# 16_seg_display_board.net
KiCad netlist of a schematic drawn in EAGLE
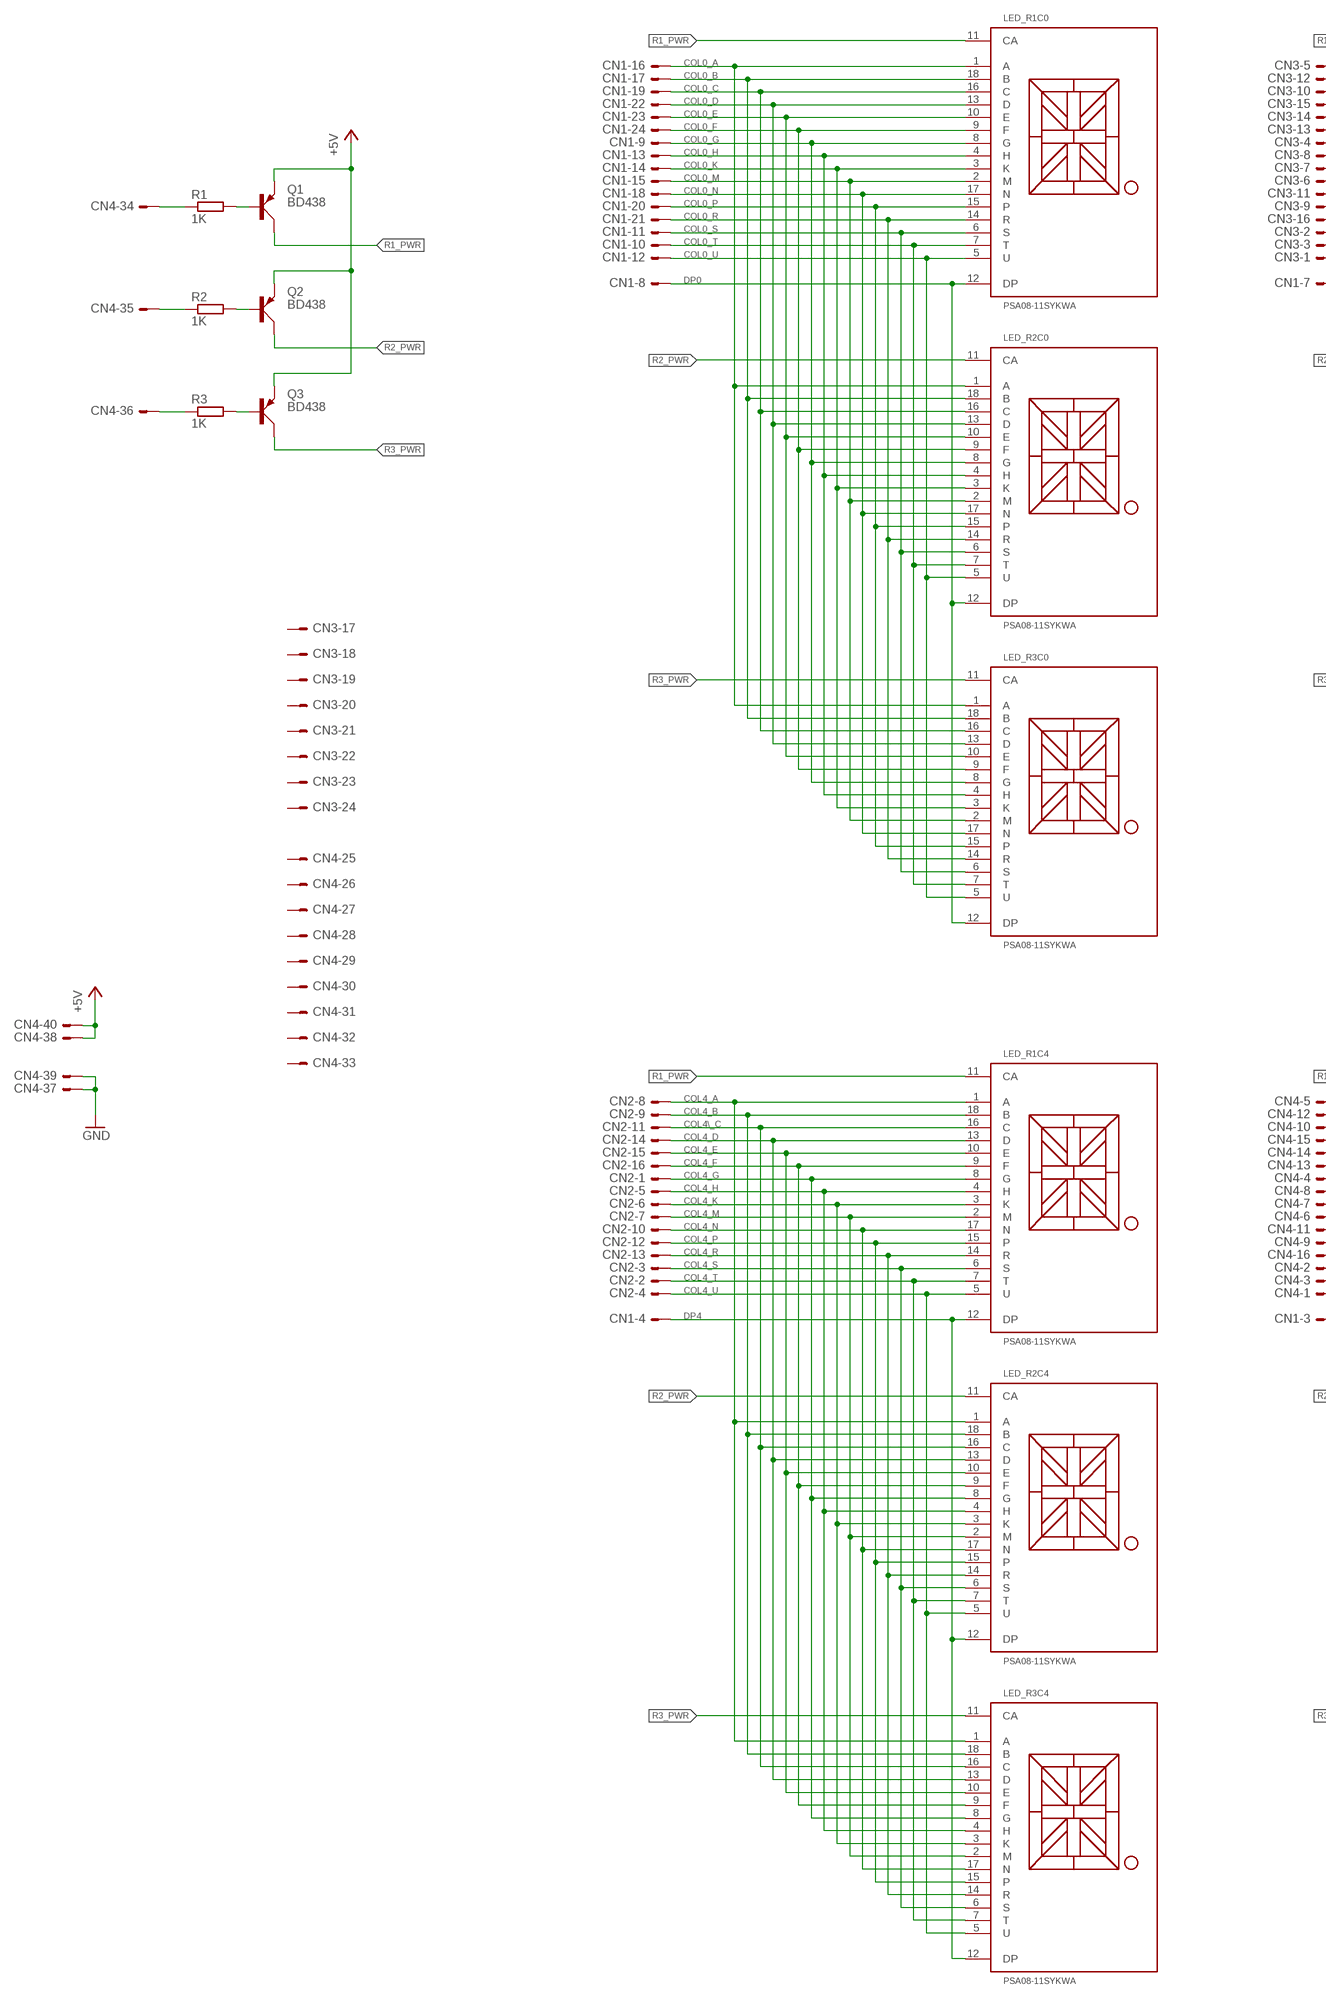
[diagram p0: schematic, sheet 1, part 1 of 2]
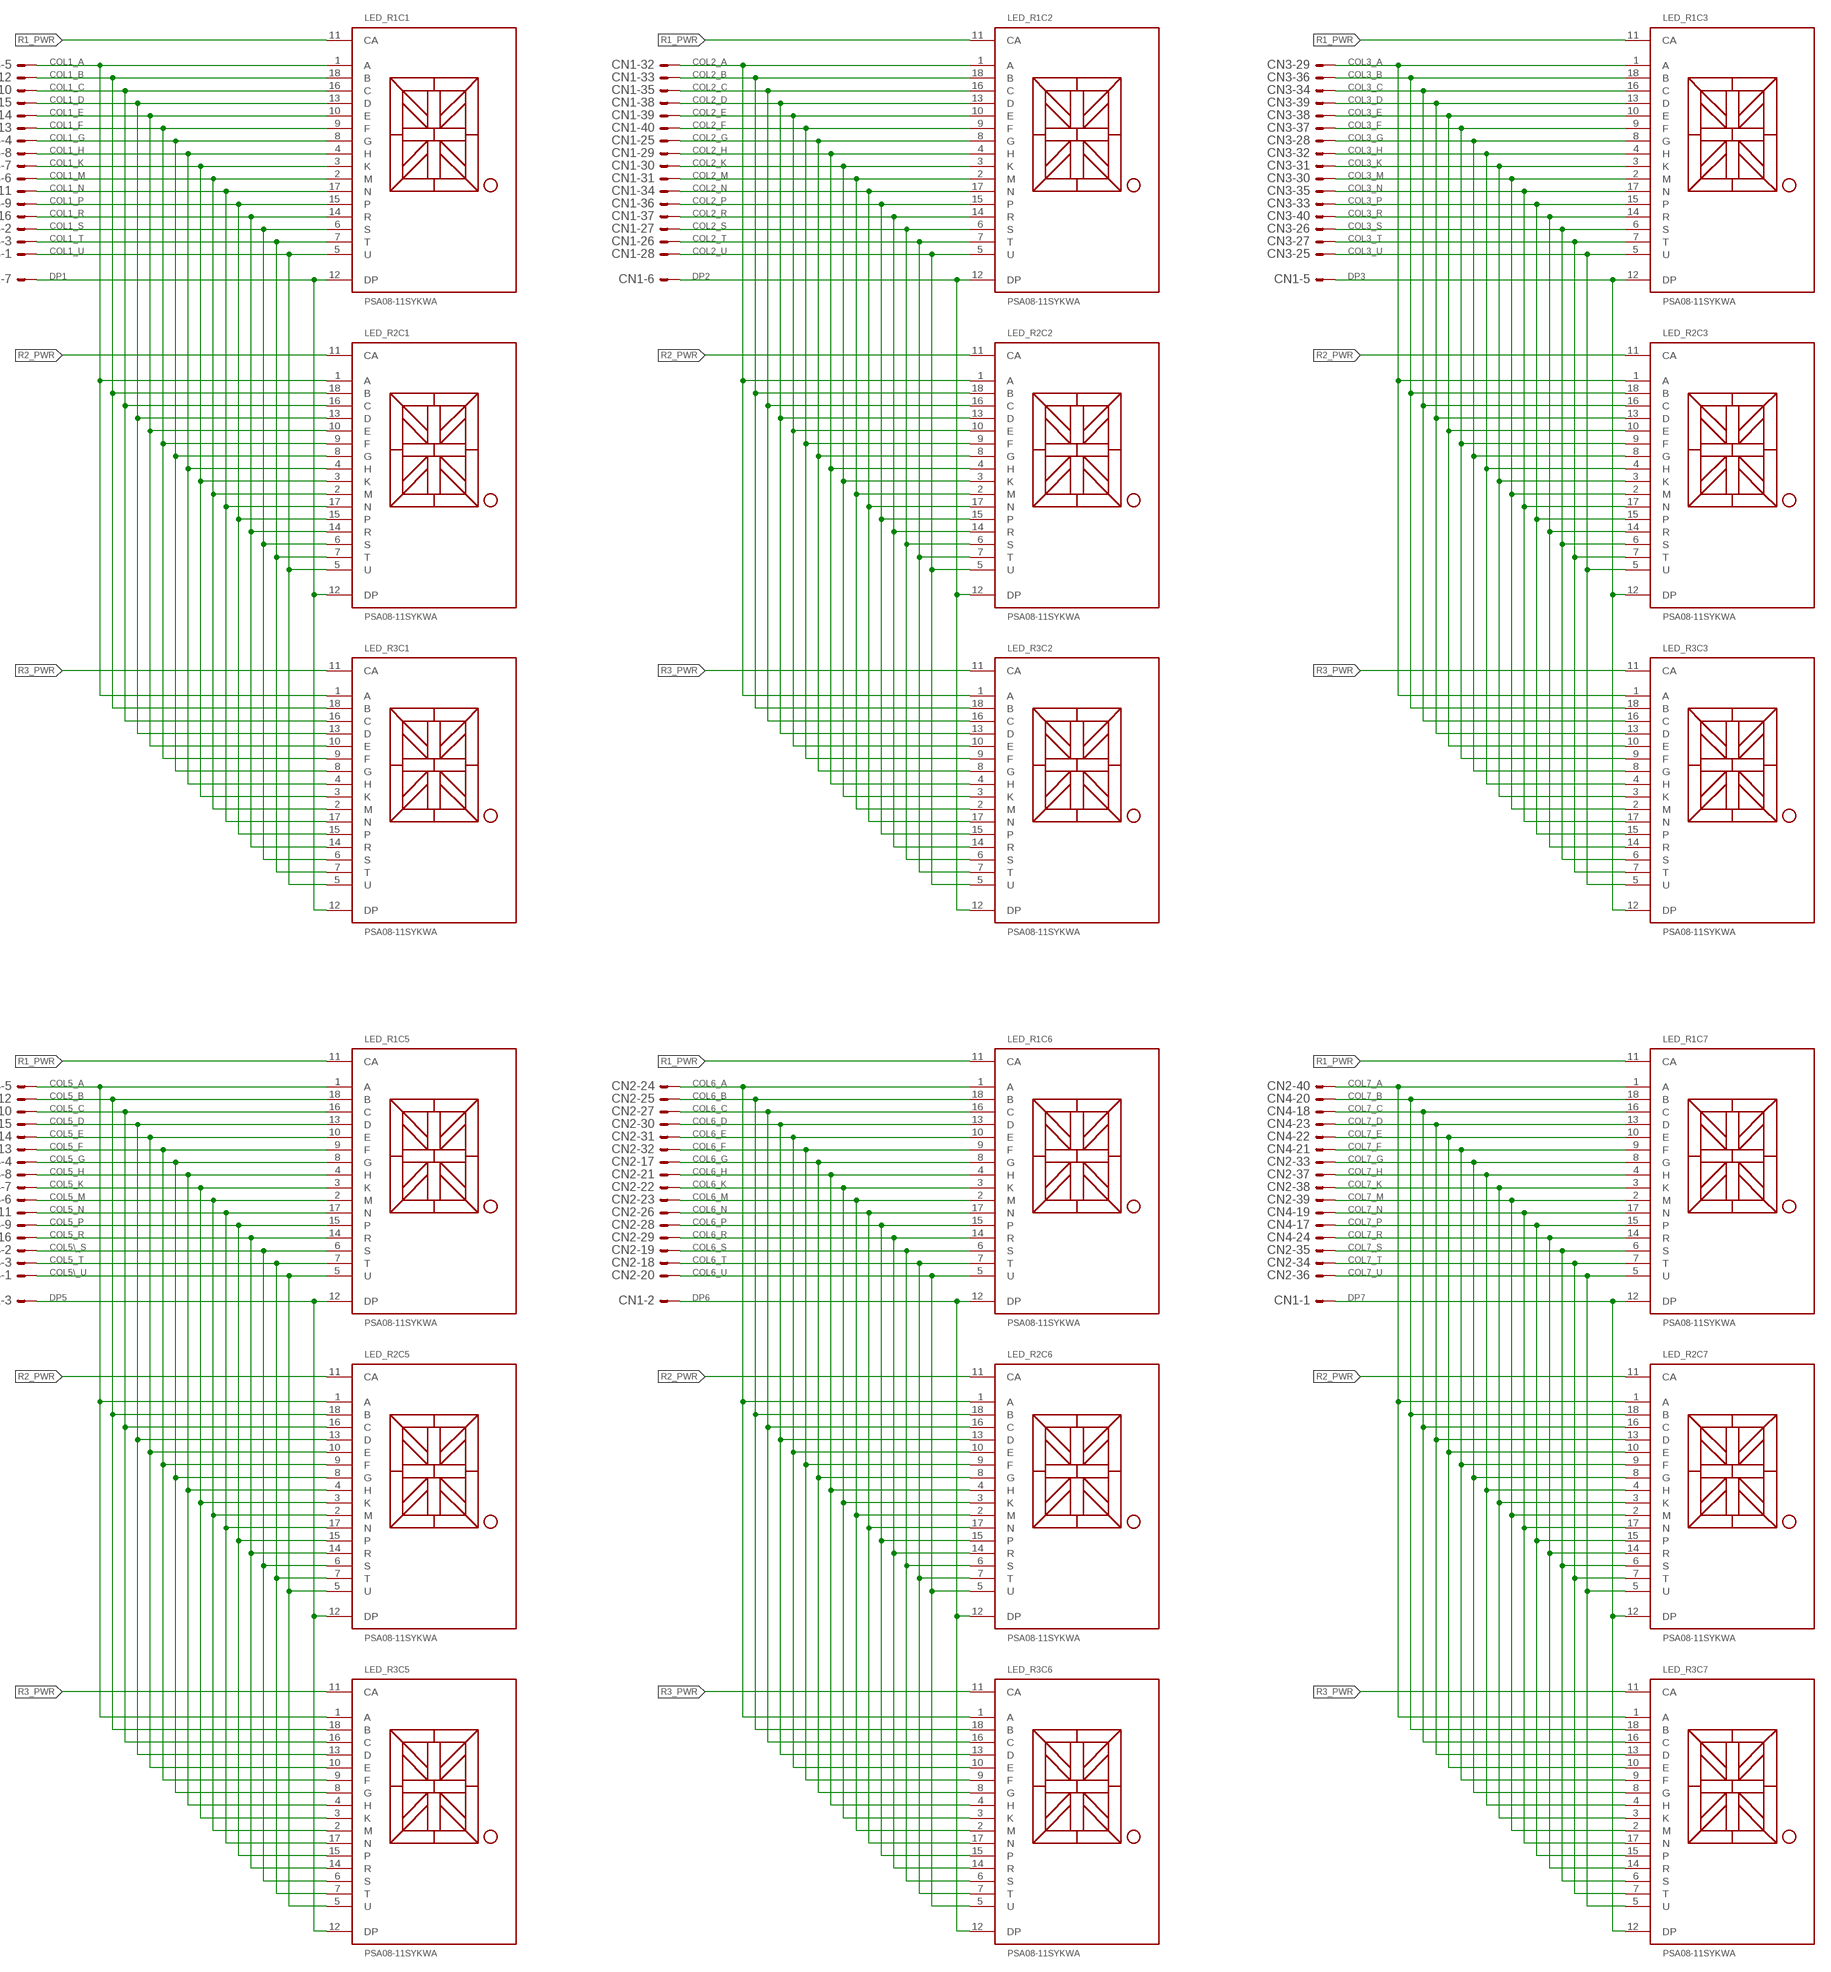
[diagram p1: schematic, sheet 1, part 2 of 2]

(export (version "E")
  (design (tool "Eeschema 10.0.6"))
  (components
    (comp (ref "CN1")
      (value "HDR40")
      (footprint "eagle-import:HDR40")
      (libsource (lib "eagle-import") (part "HDR40"))
    )
    (comp (ref "CN2")
      (value "HDR40")
      (footprint "eagle-import:HDR40")
      (libsource (lib "eagle-import") (part "HDR40"))
    )
    (comp (ref "CN3")
      (value "HDR40")
      (footprint "eagle-import:HDR40")
      (libsource (lib "eagle-import") (part "HDR40"))
    )
    (comp (ref "CN4")
      (value "HDR40")
      (footprint "eagle-import:HDR40")
      (libsource (lib "eagle-import") (part "HDR40"))
    )
    (comp (ref "LED_R1C0")
      (value "PSA08-11SYKWA")
      (footprint "eagle-import:PSA08-11SYKWA")
      (libsource (lib "eagle-import") (part "PSA08-11SYKWA"))
    )
    (comp (ref "LED_R1C1")
      (value "PSA08-11SYKWA")
      (footprint "eagle-import:PSA08-11SYKWA")
      (libsource (lib "eagle-import") (part "PSA08-11SYKWA"))
    )
    (comp (ref "LED_R1C2")
      (value "PSA08-11SYKWA")
      (footprint "eagle-import:PSA08-11SYKWA")
      (libsource (lib "eagle-import") (part "PSA08-11SYKWA"))
    )
    (comp (ref "LED_R1C3")
      (value "PSA08-11SYKWA")
      (footprint "eagle-import:PSA08-11SYKWA")
      (libsource (lib "eagle-import") (part "PSA08-11SYKWA"))
    )
    (comp (ref "LED_R1C4")
      (value "PSA08-11SYKWA")
      (footprint "eagle-import:PSA08-11SYKWA")
      (libsource (lib "eagle-import") (part "PSA08-11SYKWA"))
    )
    (comp (ref "LED_R1C5")
      (value "PSA08-11SYKWA")
      (footprint "eagle-import:PSA08-11SYKWA")
      (libsource (lib "eagle-import") (part "PSA08-11SYKWA"))
    )
    (comp (ref "LED_R1C6")
      (value "PSA08-11SYKWA")
      (footprint "eagle-import:PSA08-11SYKWA")
      (libsource (lib "eagle-import") (part "PSA08-11SYKWA"))
    )
    (comp (ref "LED_R1C7")
      (value "PSA08-11SYKWA")
      (footprint "eagle-import:PSA08-11SYKWA")
      (libsource (lib "eagle-import") (part "PSA08-11SYKWA"))
    )
    (comp (ref "LED_R2C0")
      (value "PSA08-11SYKWA")
      (footprint "eagle-import:PSA08-11SYKWA")
      (libsource (lib "eagle-import") (part "PSA08-11SYKWA"))
    )
    (comp (ref "LED_R2C1")
      (value "PSA08-11SYKWA")
      (footprint "eagle-import:PSA08-11SYKWA")
      (libsource (lib "eagle-import") (part "PSA08-11SYKWA"))
    )
    (comp (ref "LED_R2C2")
      (value "PSA08-11SYKWA")
      (footprint "eagle-import:PSA08-11SYKWA")
      (libsource (lib "eagle-import") (part "PSA08-11SYKWA"))
    )
    (comp (ref "LED_R2C3")
      (value "PSA08-11SYKWA")
      (footprint "eagle-import:PSA08-11SYKWA")
      (libsource (lib "eagle-import") (part "PSA08-11SYKWA"))
    )
    (comp (ref "LED_R2C4")
      (value "PSA08-11SYKWA")
      (footprint "eagle-import:PSA08-11SYKWA")
      (libsource (lib "eagle-import") (part "PSA08-11SYKWA"))
    )
    (comp (ref "LED_R2C5")
      (value "PSA08-11SYKWA")
      (footprint "eagle-import:PSA08-11SYKWA")
      (libsource (lib "eagle-import") (part "PSA08-11SYKWA"))
    )
    (comp (ref "LED_R2C6")
      (value "PSA08-11SYKWA")
      (footprint "eagle-import:PSA08-11SYKWA")
      (libsource (lib "eagle-import") (part "PSA08-11SYKWA"))
    )
    (comp (ref "LED_R2C7")
      (value "PSA08-11SYKWA")
      (footprint "eagle-import:PSA08-11SYKWA")
      (libsource (lib "eagle-import") (part "PSA08-11SYKWA"))
    )
    (comp (ref "LED_R3C0")
      (value "PSA08-11SYKWA")
      (footprint "eagle-import:PSA08-11SYKWA")
      (libsource (lib "eagle-import") (part "PSA08-11SYKWA"))
    )
    (comp (ref "LED_R3C1")
      (value "PSA08-11SYKWA")
      (footprint "eagle-import:PSA08-11SYKWA")
      (libsource (lib "eagle-import") (part "PSA08-11SYKWA"))
    )
    (comp (ref "LED_R3C2")
      (value "PSA08-11SYKWA")
      (footprint "eagle-import:PSA08-11SYKWA")
      (libsource (lib "eagle-import") (part "PSA08-11SYKWA"))
    )
    (comp (ref "LED_R3C3")
      (value "PSA08-11SYKWA")
      (footprint "eagle-import:PSA08-11SYKWA")
      (libsource (lib "eagle-import") (part "PSA08-11SYKWA"))
    )
    (comp (ref "LED_R3C4")
      (value "PSA08-11SYKWA")
      (footprint "eagle-import:PSA08-11SYKWA")
      (libsource (lib "eagle-import") (part "PSA08-11SYKWA"))
    )
    (comp (ref "LED_R3C5")
      (value "PSA08-11SYKWA")
      (footprint "eagle-import:PSA08-11SYKWA")
      (libsource (lib "eagle-import") (part "PSA08-11SYKWA"))
    )
    (comp (ref "LED_R3C6")
      (value "PSA08-11SYKWA")
      (footprint "eagle-import:PSA08-11SYKWA")
      (libsource (lib "eagle-import") (part "PSA08-11SYKWA"))
    )
    (comp (ref "LED_R3C7")
      (value "PSA08-11SYKWA")
      (footprint "eagle-import:PSA08-11SYKWA")
      (libsource (lib "eagle-import") (part "PSA08-11SYKWA"))
    )
    (comp (ref "Q1")
      (value "BD438")
      (footprint "eagle-import:TO126AV")
      (libsource (lib "eagle-import") (part "BD438"))
    )
    (comp (ref "Q2")
      (value "BD438")
      (footprint "eagle-import:TO126AV")
      (libsource (lib "eagle-import") (part "BD438"))
    )
    (comp (ref "Q3")
      (value "BD438")
      (footprint "eagle-import:TO126AV")
      (libsource (lib "eagle-import") (part "BD438"))
    )
    (comp (ref "R1")
      (value "1K")
      (footprint "eagle-import:0207_10")
      (libsource (lib "eagle-import") (part "R-EU_0207/10"))
    )
    (comp (ref "R2")
      (value "1K")
      (footprint "eagle-import:0207_10")
      (libsource (lib "eagle-import") (part "R-EU_0207/10"))
    )
    (comp (ref "R3")
      (value "1K")
      (footprint "eagle-import:0207_10")
      (libsource (lib "eagle-import") (part "R-EU_0207/10"))
    )
  )
  (nets
    (net (code "1") (name "+5V") (class "Default")
      (node (ref "CN4") (pin "38") (pinfunction "S_38") (pintype "passive"))
      (node (ref "CN4") (pin "40") (pinfunction "S_40") (pintype "passive"))
      (node (ref "Q1") (pin "E") (pinfunction "E_E") (pintype "passive"))
      (node (ref "Q2") (pin "E") (pinfunction "E_E") (pintype "passive"))
      (node (ref "Q3") (pin "E") (pinfunction "E_E") (pintype "passive"))
    )
    (net (code "2") (name "/COL0_A") (class "Default")
      (node (ref "CN1") (pin "16") (pinfunction "S_16") (pintype "passive"))
      (node (ref "LED_R1C0") (pin "1") (pinfunction "A_1") (pintype "input"))
      (node (ref "LED_R2C0") (pin "1") (pinfunction "A_1") (pintype "input"))
      (node (ref "LED_R3C0") (pin "1") (pinfunction "A_1") (pintype "input"))
    )
    (net (code "3") (name "/COL0_B") (class "Default")
      (node (ref "CN1") (pin "17") (pinfunction "S_17") (pintype "passive"))
      (node (ref "LED_R1C0") (pin "18") (pinfunction "B_18") (pintype "input"))
      (node (ref "LED_R2C0") (pin "18") (pinfunction "B_18") (pintype "input"))
      (node (ref "LED_R3C0") (pin "18") (pinfunction "B_18") (pintype "input"))
    )
    (net (code "4") (name "/COL0_C") (class "Default")
      (node (ref "CN1") (pin "19") (pinfunction "S_19") (pintype "passive"))
      (node (ref "LED_R1C0") (pin "16") (pinfunction "C_16") (pintype "input"))
      (node (ref "LED_R2C0") (pin "16") (pinfunction "C_16") (pintype "input"))
      (node (ref "LED_R3C0") (pin "16") (pinfunction "C_16") (pintype "input"))
    )
    (net (code "5") (name "/COL0_D") (class "Default")
      (node (ref "CN1") (pin "22") (pinfunction "S_22") (pintype "passive"))
      (node (ref "LED_R1C0") (pin "13") (pinfunction "D_13") (pintype "input"))
      (node (ref "LED_R2C0") (pin "13") (pinfunction "D_13") (pintype "input"))
      (node (ref "LED_R3C0") (pin "13") (pinfunction "D_13") (pintype "input"))
    )
    (net (code "6") (name "/COL0_E") (class "Default")
      (node (ref "CN1") (pin "23") (pinfunction "S_23") (pintype "passive"))
      (node (ref "LED_R1C0") (pin "10") (pinfunction "E_10") (pintype "input"))
      (node (ref "LED_R2C0") (pin "10") (pinfunction "E_10") (pintype "input"))
      (node (ref "LED_R3C0") (pin "10") (pinfunction "E_10") (pintype "input"))
    )
    (net (code "7") (name "/COL0_F") (class "Default")
      (node (ref "CN1") (pin "24") (pinfunction "S_24") (pintype "passive"))
      (node (ref "LED_R1C0") (pin "9") (pinfunction "F_9") (pintype "input"))
      (node (ref "LED_R2C0") (pin "9") (pinfunction "F_9") (pintype "input"))
      (node (ref "LED_R3C0") (pin "9") (pinfunction "F_9") (pintype "input"))
    )
    (net (code "8") (name "/COL0_G") (class "Default")
      (node (ref "CN1") (pin "9") (pinfunction "S_9") (pintype "passive"))
      (node (ref "LED_R1C0") (pin "8") (pinfunction "G_8") (pintype "input"))
      (node (ref "LED_R2C0") (pin "8") (pinfunction "G_8") (pintype "input"))
      (node (ref "LED_R3C0") (pin "8") (pinfunction "G_8") (pintype "input"))
    )
    (net (code "9") (name "/COL0_H") (class "Default")
      (node (ref "CN1") (pin "13") (pinfunction "S_13") (pintype "passive"))
      (node (ref "LED_R1C0") (pin "4") (pinfunction "H_4") (pintype "input"))
      (node (ref "LED_R2C0") (pin "4") (pinfunction "H_4") (pintype "input"))
      (node (ref "LED_R3C0") (pin "4") (pinfunction "H_4") (pintype "input"))
    )
    (net (code "10") (name "/COL0_K") (class "Default")
      (node (ref "CN1") (pin "14") (pinfunction "S_14") (pintype "passive"))
      (node (ref "LED_R1C0") (pin "3") (pinfunction "K_3") (pintype "input"))
      (node (ref "LED_R2C0") (pin "3") (pinfunction "K_3") (pintype "input"))
      (node (ref "LED_R3C0") (pin "3") (pinfunction "K_3") (pintype "input"))
    )
    (net (code "11") (name "/COL0_M") (class "Default")
      (node (ref "CN1") (pin "15") (pinfunction "S_15") (pintype "passive"))
      (node (ref "LED_R1C0") (pin "2") (pinfunction "M_2") (pintype "input"))
      (node (ref "LED_R2C0") (pin "2") (pinfunction "M_2") (pintype "input"))
      (node (ref "LED_R3C0") (pin "2") (pinfunction "M_2") (pintype "input"))
    )
    (net (code "12") (name "/COL0_N") (class "Default")
      (node (ref "CN1") (pin "18") (pinfunction "S_18") (pintype "passive"))
      (node (ref "LED_R1C0") (pin "17") (pinfunction "N_17") (pintype "input"))
      (node (ref "LED_R2C0") (pin "17") (pinfunction "N_17") (pintype "input"))
      (node (ref "LED_R3C0") (pin "17") (pinfunction "N_17") (pintype "input"))
    )
    (net (code "13") (name "/COL0_P") (class "Default")
      (node (ref "CN1") (pin "20") (pinfunction "S_20") (pintype "passive"))
      (node (ref "LED_R1C0") (pin "15") (pinfunction "P_15") (pintype "input"))
      (node (ref "LED_R2C0") (pin "15") (pinfunction "P_15") (pintype "input"))
      (node (ref "LED_R3C0") (pin "15") (pinfunction "P_15") (pintype "input"))
    )
    (net (code "14") (name "/COL0_R") (class "Default")
      (node (ref "CN1") (pin "21") (pinfunction "S_21") (pintype "passive"))
      (node (ref "LED_R1C0") (pin "14") (pinfunction "R_14") (pintype "input"))
      (node (ref "LED_R2C0") (pin "14") (pinfunction "R_14") (pintype "input"))
      (node (ref "LED_R3C0") (pin "14") (pinfunction "R_14") (pintype "input"))
    )
    (net (code "15") (name "/COL0_S") (class "Default")
      (node (ref "CN1") (pin "11") (pinfunction "S_11") (pintype "passive"))
      (node (ref "LED_R1C0") (pin "6") (pinfunction "S_6") (pintype "input"))
      (node (ref "LED_R2C0") (pin "6") (pinfunction "S_6") (pintype "input"))
      (node (ref "LED_R3C0") (pin "6") (pinfunction "S_6") (pintype "input"))
    )
    (net (code "16") (name "/COL0_T") (class "Default")
      (node (ref "CN1") (pin "10") (pinfunction "S_10") (pintype "passive"))
      (node (ref "LED_R1C0") (pin "7") (pinfunction "T_7") (pintype "input"))
      (node (ref "LED_R2C0") (pin "7") (pinfunction "T_7") (pintype "input"))
      (node (ref "LED_R3C0") (pin "7") (pinfunction "T_7") (pintype "input"))
    )
    (net (code "17") (name "/COL0_U") (class "Default")
      (node (ref "CN1") (pin "12") (pinfunction "S_12") (pintype "passive"))
      (node (ref "LED_R1C0") (pin "5") (pinfunction "U_5") (pintype "input"))
      (node (ref "LED_R2C0") (pin "5") (pinfunction "U_5") (pintype "input"))
      (node (ref "LED_R3C0") (pin "5") (pinfunction "U_5") (pintype "input"))
    )
    (net (code "18") (name "/COL1_A") (class "Default")
      (node (ref "CN3") (pin "5") (pinfunction "S_5") (pintype "passive"))
      (node (ref "LED_R1C1") (pin "1") (pinfunction "A_1") (pintype "input"))
      (node (ref "LED_R2C1") (pin "1") (pinfunction "A_1") (pintype "input"))
      (node (ref "LED_R3C1") (pin "1") (pinfunction "A_1") (pintype "input"))
    )
    (net (code "19") (name "/COL1_B") (class "Default")
      (node (ref "CN3") (pin "12") (pinfunction "S_12") (pintype "passive"))
      (node (ref "LED_R1C1") (pin "18") (pinfunction "B_18") (pintype "input"))
      (node (ref "LED_R2C1") (pin "18") (pinfunction "B_18") (pintype "input"))
      (node (ref "LED_R3C1") (pin "18") (pinfunction "B_18") (pintype "input"))
    )
    (net (code "20") (name "/COL1_C") (class "Default")
      (node (ref "CN3") (pin "10") (pinfunction "S_10") (pintype "passive"))
      (node (ref "LED_R1C1") (pin "16") (pinfunction "C_16") (pintype "input"))
      (node (ref "LED_R2C1") (pin "16") (pinfunction "C_16") (pintype "input"))
      (node (ref "LED_R3C1") (pin "16") (pinfunction "C_16") (pintype "input"))
    )
    (net (code "21") (name "/COL1_D") (class "Default")
      (node (ref "CN3") (pin "15") (pinfunction "S_15") (pintype "passive"))
      (node (ref "LED_R1C1") (pin "13") (pinfunction "D_13") (pintype "input"))
      (node (ref "LED_R2C1") (pin "13") (pinfunction "D_13") (pintype "input"))
      (node (ref "LED_R3C1") (pin "13") (pinfunction "D_13") (pintype "input"))
    )
    (net (code "22") (name "/COL1_E") (class "Default")
      (node (ref "CN3") (pin "14") (pinfunction "S_14") (pintype "passive"))
      (node (ref "LED_R1C1") (pin "10") (pinfunction "E_10") (pintype "input"))
      (node (ref "LED_R2C1") (pin "10") (pinfunction "E_10") (pintype "input"))
      (node (ref "LED_R3C1") (pin "10") (pinfunction "E_10") (pintype "input"))
    )
    (net (code "23") (name "/COL1_F") (class "Default")
      (node (ref "CN3") (pin "13") (pinfunction "S_13") (pintype "passive"))
      (node (ref "LED_R1C1") (pin "9") (pinfunction "F_9") (pintype "input"))
      (node (ref "LED_R2C1") (pin "9") (pinfunction "F_9") (pintype "input"))
      (node (ref "LED_R3C1") (pin "9") (pinfunction "F_9") (pintype "input"))
    )
    (net (code "24") (name "/COL1_G") (class "Default")
      (node (ref "CN3") (pin "4") (pinfunction "S_4") (pintype "passive"))
      (node (ref "LED_R1C1") (pin "8") (pinfunction "G_8") (pintype "input"))
      (node (ref "LED_R2C1") (pin "8") (pinfunction "G_8") (pintype "input"))
      (node (ref "LED_R3C1") (pin "8") (pinfunction "G_8") (pintype "input"))
    )
    (net (code "25") (name "/COL1_H") (class "Default")
      (node (ref "CN3") (pin "8") (pinfunction "S_8") (pintype "passive"))
      (node (ref "LED_R1C1") (pin "4") (pinfunction "H_4") (pintype "input"))
      (node (ref "LED_R2C1") (pin "4") (pinfunction "H_4") (pintype "input"))
      (node (ref "LED_R3C1") (pin "4") (pinfunction "H_4") (pintype "input"))
    )
    (net (code "26") (name "/COL1_K") (class "Default")
      (node (ref "CN3") (pin "7") (pinfunction "S_7") (pintype "passive"))
      (node (ref "LED_R1C1") (pin "3") (pinfunction "K_3") (pintype "input"))
      (node (ref "LED_R2C1") (pin "3") (pinfunction "K_3") (pintype "input"))
      (node (ref "LED_R3C1") (pin "3") (pinfunction "K_3") (pintype "input"))
    )
    (net (code "27") (name "/COL1_M") (class "Default")
      (node (ref "CN3") (pin "6") (pinfunction "S_6") (pintype "passive"))
      (node (ref "LED_R1C1") (pin "2") (pinfunction "M_2") (pintype "input"))
      (node (ref "LED_R2C1") (pin "2") (pinfunction "M_2") (pintype "input"))
      (node (ref "LED_R3C1") (pin "2") (pinfunction "M_2") (pintype "input"))
    )
    (net (code "28") (name "/COL1_N") (class "Default")
      (node (ref "CN3") (pin "11") (pinfunction "S_11") (pintype "passive"))
      (node (ref "LED_R1C1") (pin "17") (pinfunction "N_17") (pintype "input"))
      (node (ref "LED_R2C1") (pin "17") (pinfunction "N_17") (pintype "input"))
      (node (ref "LED_R3C1") (pin "17") (pinfunction "N_17") (pintype "input"))
    )
    (net (code "29") (name "/COL1_P") (class "Default")
      (node (ref "CN3") (pin "9") (pinfunction "S_9") (pintype "passive"))
      (node (ref "LED_R1C1") (pin "15") (pinfunction "P_15") (pintype "input"))
      (node (ref "LED_R2C1") (pin "15") (pinfunction "P_15") (pintype "input"))
      (node (ref "LED_R3C1") (pin "15") (pinfunction "P_15") (pintype "input"))
    )
    (net (code "30") (name "/COL1_R") (class "Default")
      (node (ref "CN3") (pin "16") (pinfunction "S_16") (pintype "passive"))
      (node (ref "LED_R1C1") (pin "14") (pinfunction "R_14") (pintype "input"))
      (node (ref "LED_R2C1") (pin "14") (pinfunction "R_14") (pintype "input"))
      (node (ref "LED_R3C1") (pin "14") (pinfunction "R_14") (pintype "input"))
    )
    (net (code "31") (name "/COL1_S") (class "Default")
      (node (ref "CN3") (pin "2") (pinfunction "S_2") (pintype "passive"))
      (node (ref "LED_R1C1") (pin "6") (pinfunction "S_6") (pintype "input"))
      (node (ref "LED_R2C1") (pin "6") (pinfunction "S_6") (pintype "input"))
      (node (ref "LED_R3C1") (pin "6") (pinfunction "S_6") (pintype "input"))
    )
    (net (code "32") (name "/COL1_T") (class "Default")
      (node (ref "CN3") (pin "3") (pinfunction "S_3") (pintype "passive"))
      (node (ref "LED_R1C1") (pin "7") (pinfunction "T_7") (pintype "input"))
      (node (ref "LED_R2C1") (pin "7") (pinfunction "T_7") (pintype "input"))
      (node (ref "LED_R3C1") (pin "7") (pinfunction "T_7") (pintype "input"))
    )
    (net (code "33") (name "/COL1_U") (class "Default")
      (node (ref "CN3") (pin "1") (pinfunction "S_1") (pintype "passive"))
      (node (ref "LED_R1C1") (pin "5") (pinfunction "U_5") (pintype "input"))
      (node (ref "LED_R2C1") (pin "5") (pinfunction "U_5") (pintype "input"))
      (node (ref "LED_R3C1") (pin "5") (pinfunction "U_5") (pintype "input"))
    )
    (net (code "34") (name "/COL2_A") (class "Default")
      (node (ref "CN1") (pin "32") (pinfunction "S_32") (pintype "passive"))
      (node (ref "LED_R1C2") (pin "1") (pinfunction "A_1") (pintype "input"))
      (node (ref "LED_R2C2") (pin "1") (pinfunction "A_1") (pintype "input"))
      (node (ref "LED_R3C2") (pin "1") (pinfunction "A_1") (pintype "input"))
    )
    (net (code "35") (name "/COL2_B") (class "Default")
      (node (ref "CN1") (pin "33") (pinfunction "S_33") (pintype "passive"))
      (node (ref "LED_R1C2") (pin "18") (pinfunction "B_18") (pintype "input"))
      (node (ref "LED_R2C2") (pin "18") (pinfunction "B_18") (pintype "input"))
      (node (ref "LED_R3C2") (pin "18") (pinfunction "B_18") (pintype "input"))
    )
    (net (code "36") (name "/COL2_C") (class "Default")
      (node (ref "CN1") (pin "35") (pinfunction "S_35") (pintype "passive"))
      (node (ref "LED_R1C2") (pin "16") (pinfunction "C_16") (pintype "input"))
      (node (ref "LED_R2C2") (pin "16") (pinfunction "C_16") (pintype "input"))
      (node (ref "LED_R3C2") (pin "16") (pinfunction "C_16") (pintype "input"))
    )
    (net (code "37") (name "/COL2_D") (class "Default")
      (node (ref "CN1") (pin "38") (pinfunction "S_38") (pintype "passive"))
      (node (ref "LED_R1C2") (pin "13") (pinfunction "D_13") (pintype "input"))
      (node (ref "LED_R2C2") (pin "13") (pinfunction "D_13") (pintype "input"))
      (node (ref "LED_R3C2") (pin "13") (pinfunction "D_13") (pintype "input"))
    )
    (net (code "38") (name "/COL2_E") (class "Default")
      (node (ref "CN1") (pin "39") (pinfunction "S_39") (pintype "passive"))
      (node (ref "LED_R1C2") (pin "10") (pinfunction "E_10") (pintype "input"))
      (node (ref "LED_R2C2") (pin "10") (pinfunction "E_10") (pintype "input"))
      (node (ref "LED_R3C2") (pin "10") (pinfunction "E_10") (pintype "input"))
    )
    (net (code "39") (name "/COL2_F") (class "Default")
      (node (ref "CN1") (pin "40") (pinfunction "S_40") (pintype "passive"))
      (node (ref "LED_R1C2") (pin "9") (pinfunction "F_9") (pintype "input"))
      (node (ref "LED_R2C2") (pin "9") (pinfunction "F_9") (pintype "input"))
      (node (ref "LED_R3C2") (pin "9") (pinfunction "F_9") (pintype "input"))
    )
    (net (code "40") (name "/COL2_G") (class "Default")
      (node (ref "CN1") (pin "25") (pinfunction "S_25") (pintype "passive"))
      (node (ref "LED_R1C2") (pin "8") (pinfunction "G_8") (pintype "input"))
      (node (ref "LED_R2C2") (pin "8") (pinfunction "G_8") (pintype "input"))
      (node (ref "LED_R3C2") (pin "8") (pinfunction "G_8") (pintype "input"))
    )
    (net (code "41") (name "/COL2_H") (class "Default")
      (node (ref "CN1") (pin "29") (pinfunction "S_29") (pintype "passive"))
      (node (ref "LED_R1C2") (pin "4") (pinfunction "H_4") (pintype "input"))
      (node (ref "LED_R2C2") (pin "4") (pinfunction "H_4") (pintype "input"))
      (node (ref "LED_R3C2") (pin "4") (pinfunction "H_4") (pintype "input"))
    )
    (net (code "42") (name "/COL2_K") (class "Default")
      (node (ref "CN1") (pin "30") (pinfunction "S_30") (pintype "passive"))
      (node (ref "LED_R1C2") (pin "3") (pinfunction "K_3") (pintype "input"))
      (node (ref "LED_R2C2") (pin "3") (pinfunction "K_3") (pintype "input"))
      (node (ref "LED_R3C2") (pin "3") (pinfunction "K_3") (pintype "input"))
    )
    (net (code "43") (name "/COL2_M") (class "Default")
      (node (ref "CN1") (pin "31") (pinfunction "S_31") (pintype "passive"))
      (node (ref "LED_R1C2") (pin "2") (pinfunction "M_2") (pintype "input"))
      (node (ref "LED_R2C2") (pin "2") (pinfunction "M_2") (pintype "input"))
      (node (ref "LED_R3C2") (pin "2") (pinfunction "M_2") (pintype "input"))
    )
    (net (code "44") (name "/COL2_N") (class "Default")
      (node (ref "CN1") (pin "34") (pinfunction "S_34") (pintype "passive"))
      (node (ref "LED_R1C2") (pin "17") (pinfunction "N_17") (pintype "input"))
      (node (ref "LED_R2C2") (pin "17") (pinfunction "N_17") (pintype "input"))
      (node (ref "LED_R3C2") (pin "17") (pinfunction "N_17") (pintype "input"))
    )
    (net (code "45") (name "/COL2_P") (class "Default")
      (node (ref "CN1") (pin "36") (pinfunction "S_36") (pintype "passive"))
      (node (ref "LED_R1C2") (pin "15") (pinfunction "P_15") (pintype "input"))
      (node (ref "LED_R2C2") (pin "15") (pinfunction "P_15") (pintype "input"))
      (node (ref "LED_R3C2") (pin "15") (pinfunction "P_15") (pintype "input"))
    )
    (net (code "46") (name "/COL2_R") (class "Default")
      (node (ref "CN1") (pin "37") (pinfunction "S_37") (pintype "passive"))
      (node (ref "LED_R1C2") (pin "14") (pinfunction "R_14") (pintype "input"))
      (node (ref "LED_R2C2") (pin "14") (pinfunction "R_14") (pintype "input"))
      (node (ref "LED_R3C2") (pin "14") (pinfunction "R_14") (pintype "input"))
    )
    (net (code "47") (name "/COL2_S") (class "Default")
      (node (ref "CN1") (pin "27") (pinfunction "S_27") (pintype "passive"))
      (node (ref "LED_R1C2") (pin "6") (pinfunction "S_6") (pintype "input"))
      (node (ref "LED_R2C2") (pin "6") (pinfunction "S_6") (pintype "input"))
      (node (ref "LED_R3C2") (pin "6") (pinfunction "S_6") (pintype "input"))
    )
    (net (code "48") (name "/COL2_T") (class "Default")
      (node (ref "CN1") (pin "26") (pinfunction "S_26") (pintype "passive"))
      (node (ref "LED_R1C2") (pin "7") (pinfunction "T_7") (pintype "input"))
      (node (ref "LED_R2C2") (pin "7") (pinfunction "T_7") (pintype "input"))
      (node (ref "LED_R3C2") (pin "7") (pinfunction "T_7") (pintype "input"))
    )
    (net (code "49") (name "/COL2_U") (class "Default")
      (node (ref "CN1") (pin "28") (pinfunction "S_28") (pintype "passive"))
      (node (ref "LED_R1C2") (pin "5") (pinfunction "U_5") (pintype "input"))
      (node (ref "LED_R2C2") (pin "5") (pinfunction "U_5") (pintype "input"))
      (node (ref "LED_R3C2") (pin "5") (pinfunction "U_5") (pintype "input"))
    )
    (net (code "50") (name "/COL3_A") (class "Default")
      (node (ref "CN3") (pin "29") (pinfunction "S_29") (pintype "passive"))
      (node (ref "LED_R1C3") (pin "1") (pinfunction "A_1") (pintype "input"))
      (node (ref "LED_R2C3") (pin "1") (pinfunction "A_1") (pintype "input"))
      (node (ref "LED_R3C3") (pin "1") (pinfunction "A_1") (pintype "input"))
    )
    (net (code "51") (name "/COL3_B") (class "Default")
      (node (ref "CN3") (pin "36") (pinfunction "S_36") (pintype "passive"))
      (node (ref "LED_R1C3") (pin "18") (pinfunction "B_18") (pintype "input"))
      (node (ref "LED_R2C3") (pin "18") (pinfunction "B_18") (pintype "input"))
      (node (ref "LED_R3C3") (pin "18") (pinfunction "B_18") (pintype "input"))
    )
    (net (code "52") (name "/COL3_C") (class "Default")
      (node (ref "CN3") (pin "34") (pinfunction "S_34") (pintype "passive"))
      (node (ref "LED_R1C3") (pin "16") (pinfunction "C_16") (pintype "input"))
      (node (ref "LED_R2C3") (pin "16") (pinfunction "C_16") (pintype "input"))
      (node (ref "LED_R3C3") (pin "16") (pinfunction "C_16") (pintype "input"))
    )
    (net (code "53") (name "/COL3_D") (class "Default")
      (node (ref "CN3") (pin "39") (pinfunction "S_39") (pintype "passive"))
      (node (ref "LED_R1C3") (pin "13") (pinfunction "D_13") (pintype "input"))
      (node (ref "LED_R2C3") (pin "13") (pinfunction "D_13") (pintype "input"))
      (node (ref "LED_R3C3") (pin "13") (pinfunction "D_13") (pintype "input"))
    )
    (net (code "54") (name "/COL3_E") (class "Default")
      (node (ref "CN3") (pin "38") (pinfunction "S_38") (pintype "passive"))
      (node (ref "LED_R1C3") (pin "10") (pinfunction "E_10") (pintype "input"))
      (node (ref "LED_R2C3") (pin "10") (pinfunction "E_10") (pintype "input"))
      (node (ref "LED_R3C3") (pin "10") (pinfunction "E_10") (pintype "input"))
    )
    (net (code "55") (name "/COL3_F") (class "Default")
      (node (ref "CN3") (pin "37") (pinfunction "S_37") (pintype "passive"))
      (node (ref "LED_R1C3") (pin "9") (pinfunction "F_9") (pintype "input"))
      (node (ref "LED_R2C3") (pin "9") (pinfunction "F_9") (pintype "input"))
      (node (ref "LED_R3C3") (pin "9") (pinfunction "F_9") (pintype "input"))
    )
    (net (code "56") (name "/COL3_G") (class "Default")
      (node (ref "CN3") (pin "28") (pinfunction "S_28") (pintype "passive"))
      (node (ref "LED_R1C3") (pin "8") (pinfunction "G_8") (pintype "input"))
      (node (ref "LED_R2C3") (pin "8") (pinfunction "G_8") (pintype "input"))
      (node (ref "LED_R3C3") (pin "8") (pinfunction "G_8") (pintype "input"))
    )
    (net (code "57") (name "/COL3_H") (class "Default")
      (node (ref "CN3") (pin "32") (pinfunction "S_32") (pintype "passive"))
      (node (ref "LED_R1C3") (pin "4") (pinfunction "H_4") (pintype "input"))
      (node (ref "LED_R2C3") (pin "4") (pinfunction "H_4") (pintype "input"))
      (node (ref "LED_R3C3") (pin "4") (pinfunction "H_4") (pintype "input"))
    )
    (net (code "58") (name "/COL3_K") (class "Default")
      (node (ref "CN3") (pin "31") (pinfunction "S_31") (pintype "passive"))
      (node (ref "LED_R1C3") (pin "3") (pinfunction "K_3") (pintype "input"))
      (node (ref "LED_R2C3") (pin "3") (pinfunction "K_3") (pintype "input"))
      (node (ref "LED_R3C3") (pin "3") (pinfunction "K_3") (pintype "input"))
    )
    (net (code "59") (name "/COL3_M") (class "Default")
      (node (ref "CN3") (pin "30") (pinfunction "S_30") (pintype "passive"))
      (node (ref "LED_R1C3") (pin "2") (pinfunction "M_2") (pintype "input"))
      (node (ref "LED_R2C3") (pin "2") (pinfunction "M_2") (pintype "input"))
      (node (ref "LED_R3C3") (pin "2") (pinfunction "M_2") (pintype "input"))
    )
    (net (code "60") (name "/COL3_N") (class "Default")
      (node (ref "CN3") (pin "35") (pinfunction "S_35") (pintype "passive"))
      (node (ref "LED_R1C3") (pin "17") (pinfunction "N_17") (pintype "input"))
      (node (ref "LED_R2C3") (pin "17") (pinfunction "N_17") (pintype "input"))
      (node (ref "LED_R3C3") (pin "17") (pinfunction "N_17") (pintype "input"))
    )
    (net (code "61") (name "/COL3_P") (class "Default")
      (node (ref "CN3") (pin "33") (pinfunction "S_33") (pintype "passive"))
      (node (ref "LED_R1C3") (pin "15") (pinfunction "P_15") (pintype "input"))
      (node (ref "LED_R2C3") (pin "15") (pinfunction "P_15") (pintype "input"))
      (node (ref "LED_R3C3") (pin "15") (pinfunction "P_15") (pintype "input"))
    )
    (net (code "62") (name "/COL3_R") (class "Default")
      (node (ref "CN3") (pin "40") (pinfunction "S_40") (pintype "passive"))
      (node (ref "LED_R1C3") (pin "14") (pinfunction "R_14") (pintype "input"))
      (node (ref "LED_R2C3") (pin "14") (pinfunction "R_14") (pintype "input"))
      (node (ref "LED_R3C3") (pin "14") (pinfunction "R_14") (pintype "input"))
    )
    (net (code "63") (name "/COL3_S") (class "Default")
      (node (ref "CN3") (pin "26") (pinfunction "S_26") (pintype "passive"))
      (node (ref "LED_R1C3") (pin "6") (pinfunction "S_6") (pintype "input"))
      (node (ref "LED_R2C3") (pin "6") (pinfunction "S_6") (pintype "input"))
      (node (ref "LED_R3C3") (pin "6") (pinfunction "S_6") (pintype "input"))
    )
    (net (code "64") (name "/COL3_T") (class "Default")
      (node (ref "CN3") (pin "27") (pinfunction "S_27") (pintype "passive"))
      (node (ref "LED_R1C3") (pin "7") (pinfunction "T_7") (pintype "input"))
      (node (ref "LED_R2C3") (pin "7") (pinfunction "T_7") (pintype "input"))
      (node (ref "LED_R3C3") (pin "7") (pinfunction "T_7") (pintype "input"))
    )
    (net (code "65") (name "/COL3_U") (class "Default")
      (node (ref "CN3") (pin "25") (pinfunction "S_25") (pintype "passive"))
      (node (ref "LED_R1C3") (pin "5") (pinfunction "U_5") (pintype "input"))
      (node (ref "LED_R2C3") (pin "5") (pinfunction "U_5") (pintype "input"))
      (node (ref "LED_R3C3") (pin "5") (pinfunction "U_5") (pintype "input"))
    )
    (net (code "66") (name "/COL4\\_C") (class "Default")
      (node (ref "CN2") (pin "11") (pinfunction "S_11") (pintype "passive"))
      (node (ref "LED_R1C4") (pin "16") (pinfunction "C_16") (pintype "input"))
      (node (ref "LED_R2C4") (pin "16") (pinfunction "C_16") (pintype "input"))
      (node (ref "LED_R3C4") (pin "16") (pinfunction "C_16") (pintype "input"))
    )
    (net (code "67") (name "/COL4_A") (class "Default")
      (node (ref "CN2") (pin "8") (pinfunction "S_8") (pintype "passive"))
      (node (ref "LED_R1C4") (pin "1") (pinfunction "A_1") (pintype "input"))
      (node (ref "LED_R2C4") (pin "1") (pinfunction "A_1") (pintype "input"))
      (node (ref "LED_R3C4") (pin "1") (pinfunction "A_1") (pintype "input"))
    )
    (net (code "68") (name "/COL4_B") (class "Default")
      (node (ref "CN2") (pin "9") (pinfunction "S_9") (pintype "passive"))
      (node (ref "LED_R1C4") (pin "18") (pinfunction "B_18") (pintype "input"))
      (node (ref "LED_R2C4") (pin "18") (pinfunction "B_18") (pintype "input"))
      (node (ref "LED_R3C4") (pin "18") (pinfunction "B_18") (pintype "input"))
    )
    (net (code "69") (name "/COL4_D") (class "Default")
      (node (ref "CN2") (pin "14") (pinfunction "S_14") (pintype "passive"))
      (node (ref "LED_R1C4") (pin "13") (pinfunction "D_13") (pintype "input"))
      (node (ref "LED_R2C4") (pin "13") (pinfunction "D_13") (pintype "input"))
      (node (ref "LED_R3C4") (pin "13") (pinfunction "D_13") (pintype "input"))
    )
    (net (code "70") (name "/COL4_E") (class "Default")
      (node (ref "CN2") (pin "15") (pinfunction "S_15") (pintype "passive"))
      (node (ref "LED_R1C4") (pin "10") (pinfunction "E_10") (pintype "input"))
      (node (ref "LED_R2C4") (pin "10") (pinfunction "E_10") (pintype "input"))
      (node (ref "LED_R3C4") (pin "10") (pinfunction "E_10") (pintype "input"))
    )
    (net (code "71") (name "/COL4_F") (class "Default")
      (node (ref "CN2") (pin "16") (pinfunction "S_16") (pintype "passive"))
      (node (ref "LED_R1C4") (pin "9") (pinfunction "F_9") (pintype "input"))
      (node (ref "LED_R2C4") (pin "9") (pinfunction "F_9") (pintype "input"))
      (node (ref "LED_R3C4") (pin "9") (pinfunction "F_9") (pintype "input"))
    )
    (net (code "72") (name "/COL4_G") (class "Default")
      (node (ref "CN2") (pin "1") (pinfunction "S_1") (pintype "passive"))
      (node (ref "LED_R1C4") (pin "8") (pinfunction "G_8") (pintype "input"))
      (node (ref "LED_R2C4") (pin "8") (pinfunction "G_8") (pintype "input"))
      (node (ref "LED_R3C4") (pin "8") (pinfunction "G_8") (pintype "input"))
    )
    (net (code "73") (name "/COL4_H") (class "Default")
      (node (ref "CN2") (pin "5") (pinfunction "S_5") (pintype "passive"))
      (node (ref "LED_R1C4") (pin "4") (pinfunction "H_4") (pintype "input"))
      (node (ref "LED_R2C4") (pin "4") (pinfunction "H_4") (pintype "input"))
      (node (ref "LED_R3C4") (pin "4") (pinfunction "H_4") (pintype "input"))
    )
    (net (code "74") (name "/COL4_K") (class "Default")
      (node (ref "CN2") (pin "6") (pinfunction "S_6") (pintype "passive"))
      (node (ref "LED_R1C4") (pin "3") (pinfunction "K_3") (pintype "input"))
      (node (ref "LED_R2C4") (pin "3") (pinfunction "K_3") (pintype "input"))
      (node (ref "LED_R3C4") (pin "3") (pinfunction "K_3") (pintype "input"))
    )
    (net (code "75") (name "/COL4_M") (class "Default")
      (node (ref "CN2") (pin "7") (pinfunction "S_7") (pintype "passive"))
      (node (ref "LED_R1C4") (pin "2") (pinfunction "M_2") (pintype "input"))
      (node (ref "LED_R2C4") (pin "2") (pinfunction "M_2") (pintype "input"))
      (node (ref "LED_R3C4") (pin "2") (pinfunction "M_2") (pintype "input"))
    )
    (net (code "76") (name "/COL4_N") (class "Default")
      (node (ref "CN2") (pin "10") (pinfunction "S_10") (pintype "passive"))
      (node (ref "LED_R1C4") (pin "17") (pinfunction "N_17") (pintype "input"))
      (node (ref "LED_R2C4") (pin "17") (pinfunction "N_17") (pintype "input"))
      (node (ref "LED_R3C4") (pin "17") (pinfunction "N_17") (pintype "input"))
    )
    (net (code "77") (name "/COL4_P") (class "Default")
      (node (ref "CN2") (pin "12") (pinfunction "S_12") (pintype "passive"))
      (node (ref "LED_R1C4") (pin "15") (pinfunction "P_15") (pintype "input"))
      (node (ref "LED_R2C4") (pin "15") (pinfunction "P_15") (pintype "input"))
      (node (ref "LED_R3C4") (pin "15") (pinfunction "P_15") (pintype "input"))
    )
    (net (code "78") (name "/COL4_R") (class "Default")
      (node (ref "CN2") (pin "13") (pinfunction "S_13") (pintype "passive"))
      (node (ref "LED_R1C4") (pin "14") (pinfunction "R_14") (pintype "input"))
      (node (ref "LED_R2C4") (pin "14") (pinfunction "R_14") (pintype "input"))
      (node (ref "LED_R3C4") (pin "14") (pinfunction "R_14") (pintype "input"))
    )
    (net (code "79") (name "/COL4_S") (class "Default")
      (node (ref "CN2") (pin "3") (pinfunction "S_3") (pintype "passive"))
      (node (ref "LED_R1C4") (pin "6") (pinfunction "S_6") (pintype "input"))
      (node (ref "LED_R2C4") (pin "6") (pinfunction "S_6") (pintype "input"))
      (node (ref "LED_R3C4") (pin "6") (pinfunction "S_6") (pintype "input"))
    )
    (net (code "80") (name "/COL4_T") (class "Default")
      (node (ref "CN2") (pin "2") (pinfunction "S_2") (pintype "passive"))
      (node (ref "LED_R1C4") (pin "7") (pinfunction "T_7") (pintype "input"))
      (node (ref "LED_R2C4") (pin "7") (pinfunction "T_7") (pintype "input"))
      (node (ref "LED_R3C4") (pin "7") (pinfunction "T_7") (pintype "input"))
    )
    (net (code "81") (name "/COL4_U") (class "Default")
      (node (ref "CN2") (pin "4") (pinfunction "S_4") (pintype "passive"))
      (node (ref "LED_R1C4") (pin "5") (pinfunction "U_5") (pintype "input"))
      (node (ref "LED_R2C4") (pin "5") (pinfunction "U_5") (pintype "input"))
      (node (ref "LED_R3C4") (pin "5") (pinfunction "U_5") (pintype "input"))
    )
    (net (code "82") (name "/COL5\\_S") (class "Default")
      (node (ref "CN4") (pin "2") (pinfunction "S_2") (pintype "passive"))
      (node (ref "LED_R1C5") (pin "6") (pinfunction "S_6") (pintype "input"))
      (node (ref "LED_R2C5") (pin "6") (pinfunction "S_6") (pintype "input"))
      (node (ref "LED_R3C5") (pin "6") (pinfunction "S_6") (pintype "input"))
    )
    (net (code "83") (name "/COL5\\_U") (class "Default")
      (node (ref "CN4") (pin "1") (pinfunction "S_1") (pintype "passive"))
      (node (ref "LED_R1C5") (pin "5") (pinfunction "U_5") (pintype "input"))
      (node (ref "LED_R2C5") (pin "5") (pinfunction "U_5") (pintype "input"))
      (node (ref "LED_R3C5") (pin "5") (pinfunction "U_5") (pintype "input"))
    )
    (net (code "84") (name "/COL5_A") (class "Default")
      (node (ref "CN4") (pin "5") (pinfunction "S_5") (pintype "passive"))
      (node (ref "LED_R1C5") (pin "1") (pinfunction "A_1") (pintype "input"))
      (node (ref "LED_R2C5") (pin "1") (pinfunction "A_1") (pintype "input"))
      (node (ref "LED_R3C5") (pin "1") (pinfunction "A_1") (pintype "input"))
    )
    (net (code "85") (name "/COL5_B") (class "Default")
      (node (ref "CN4") (pin "12") (pinfunction "S_12") (pintype "passive"))
      (node (ref "LED_R1C5") (pin "18") (pinfunction "B_18") (pintype "input"))
      (node (ref "LED_R2C5") (pin "18") (pinfunction "B_18") (pintype "input"))
      (node (ref "LED_R3C5") (pin "18") (pinfunction "B_18") (pintype "input"))
    )
    (net (code "86") (name "/COL5_C") (class "Default")
      (node (ref "CN4") (pin "10") (pinfunction "S_10") (pintype "passive"))
      (node (ref "LED_R1C5") (pin "16") (pinfunction "C_16") (pintype "input"))
      (node (ref "LED_R2C5") (pin "16") (pinfunction "C_16") (pintype "input"))
      (node (ref "LED_R3C5") (pin "16") (pinfunction "C_16") (pintype "input"))
    )
    (net (code "87") (name "/COL5_D") (class "Default")
      (node (ref "CN4") (pin "15") (pinfunction "S_15") (pintype "passive"))
      (node (ref "LED_R1C5") (pin "13") (pinfunction "D_13") (pintype "input"))
      (node (ref "LED_R2C5") (pin "13") (pinfunction "D_13") (pintype "input"))
      (node (ref "LED_R3C5") (pin "13") (pinfunction "D_13") (pintype "input"))
    )
    (net (code "88") (name "/COL5_E") (class "Default")
      (node (ref "CN4") (pin "14") (pinfunction "S_14") (pintype "passive"))
      (node (ref "LED_R1C5") (pin "10") (pinfunction "E_10") (pintype "input"))
      (node (ref "LED_R2C5") (pin "10") (pinfunction "E_10") (pintype "input"))
      (node (ref "LED_R3C5") (pin "10") (pinfunction "E_10") (pintype "input"))
    )
    (net (code "89") (name "/COL5_F") (class "Default")
      (node (ref "CN4") (pin "13") (pinfunction "S_13") (pintype "passive"))
      (node (ref "LED_R1C5") (pin "9") (pinfunction "F_9") (pintype "input"))
      (node (ref "LED_R2C5") (pin "9") (pinfunction "F_9") (pintype "input"))
      (node (ref "LED_R3C5") (pin "9") (pinfunction "F_9") (pintype "input"))
    )
    (net (code "90") (name "/COL5_G") (class "Default")
      (node (ref "CN4") (pin "4") (pinfunction "S_4") (pintype "passive"))
      (node (ref "LED_R1C5") (pin "8") (pinfunction "G_8") (pintype "input"))
      (node (ref "LED_R2C5") (pin "8") (pinfunction "G_8") (pintype "input"))
      (node (ref "LED_R3C5") (pin "8") (pinfunction "G_8") (pintype "input"))
    )
    (net (code "91") (name "/COL5_H") (class "Default")
      (node (ref "CN4") (pin "8") (pinfunction "S_8") (pintype "passive"))
      (node (ref "LED_R1C5") (pin "4") (pinfunction "H_4") (pintype "input"))
      (node (ref "LED_R2C5") (pin "4") (pinfunction "H_4") (pintype "input"))
      (node (ref "LED_R3C5") (pin "4") (pinfunction "H_4") (pintype "input"))
    )
    (net (code "92") (name "/COL5_K") (class "Default")
      (node (ref "CN4") (pin "7") (pinfunction "S_7") (pintype "passive"))
      (node (ref "LED_R1C5") (pin "3") (pinfunction "K_3") (pintype "input"))
      (node (ref "LED_R2C5") (pin "3") (pinfunction "K_3") (pintype "input"))
      (node (ref "LED_R3C5") (pin "3") (pinfunction "K_3") (pintype "input"))
    )
    (net (code "93") (name "/COL5_M") (class "Default")
      (node (ref "CN4") (pin "6") (pinfunction "S_6") (pintype "passive"))
      (node (ref "LED_R1C5") (pin "2") (pinfunction "M_2") (pintype "input"))
      (node (ref "LED_R2C5") (pin "2") (pinfunction "M_2") (pintype "input"))
      (node (ref "LED_R3C5") (pin "2") (pinfunction "M_2") (pintype "input"))
    )
    (net (code "94") (name "/COL5_N") (class "Default")
      (node (ref "CN4") (pin "11") (pinfunction "S_11") (pintype "passive"))
      (node (ref "LED_R1C5") (pin "17") (pinfunction "N_17") (pintype "input"))
      (node (ref "LED_R2C5") (pin "17") (pinfunction "N_17") (pintype "input"))
      (node (ref "LED_R3C5") (pin "17") (pinfunction "N_17") (pintype "input"))
    )
    (net (code "95") (name "/COL5_P") (class "Default")
      (node (ref "CN4") (pin "9") (pinfunction "S_9") (pintype "passive"))
      (node (ref "LED_R1C5") (pin "15") (pinfunction "P_15") (pintype "input"))
      (node (ref "LED_R2C5") (pin "15") (pinfunction "P_15") (pintype "input"))
      (node (ref "LED_R3C5") (pin "15") (pinfunction "P_15") (pintype "input"))
    )
    (net (code "96") (name "/COL5_R") (class "Default")
      (node (ref "CN4") (pin "16") (pinfunction "S_16") (pintype "passive"))
      (node (ref "LED_R1C5") (pin "14") (pinfunction "R_14") (pintype "input"))
      (node (ref "LED_R2C5") (pin "14") (pinfunction "R_14") (pintype "input"))
      (node (ref "LED_R3C5") (pin "14") (pinfunction "R_14") (pintype "input"))
    )
    (net (code "97") (name "/COL5_T") (class "Default")
      (node (ref "CN4") (pin "3") (pinfunction "S_3") (pintype "passive"))
      (node (ref "LED_R1C5") (pin "7") (pinfunction "T_7") (pintype "input"))
      (node (ref "LED_R2C5") (pin "7") (pinfunction "T_7") (pintype "input"))
      (node (ref "LED_R3C5") (pin "7") (pinfunction "T_7") (pintype "input"))
    )
    (net (code "98") (name "/COL6_A") (class "Default")
      (node (ref "CN2") (pin "24") (pinfunction "S_24") (pintype "passive"))
      (node (ref "LED_R1C6") (pin "1") (pinfunction "A_1") (pintype "input"))
      (node (ref "LED_R2C6") (pin "1") (pinfunction "A_1") (pintype "input"))
      (node (ref "LED_R3C6") (pin "1") (pinfunction "A_1") (pintype "input"))
    )
    (net (code "99") (name "/COL6_B") (class "Default")
      (node (ref "CN2") (pin "25") (pinfunction "S_25") (pintype "passive"))
      (node (ref "LED_R1C6") (pin "18") (pinfunction "B_18") (pintype "input"))
      (node (ref "LED_R2C6") (pin "18") (pinfunction "B_18") (pintype "input"))
      (node (ref "LED_R3C6") (pin "18") (pinfunction "B_18") (pintype "input"))
    )
    (net (code "100") (name "/COL6_C") (class "Default")
      (node (ref "CN2") (pin "27") (pinfunction "S_27") (pintype "passive"))
      (node (ref "LED_R1C6") (pin "16") (pinfunction "C_16") (pintype "input"))
      (node (ref "LED_R2C6") (pin "16") (pinfunction "C_16") (pintype "input"))
      (node (ref "LED_R3C6") (pin "16") (pinfunction "C_16") (pintype "input"))
    )
    (net (code "101") (name "/COL6_D") (class "Default")
      (node (ref "CN2") (pin "30") (pinfunction "S_30") (pintype "passive"))
      (node (ref "LED_R1C6") (pin "13") (pinfunction "D_13") (pintype "input"))
      (node (ref "LED_R2C6") (pin "13") (pinfunction "D_13") (pintype "input"))
      (node (ref "LED_R3C6") (pin "13") (pinfunction "D_13") (pintype "input"))
    )
    (net (code "102") (name "/COL6_E") (class "Default")
      (node (ref "CN2") (pin "31") (pinfunction "S_31") (pintype "passive"))
      (node (ref "LED_R1C6") (pin "10") (pinfunction "E_10") (pintype "input"))
      (node (ref "LED_R2C6") (pin "10") (pinfunction "E_10") (pintype "input"))
      (node (ref "LED_R3C6") (pin "10") (pinfunction "E_10") (pintype "input"))
    )
    (net (code "103") (name "/COL6_F") (class "Default")
      (node (ref "CN2") (pin "32") (pinfunction "S_32") (pintype "passive"))
      (node (ref "LED_R1C6") (pin "9") (pinfunction "F_9") (pintype "input"))
      (node (ref "LED_R2C6") (pin "9") (pinfunction "F_9") (pintype "input"))
      (node (ref "LED_R3C6") (pin "9") (pinfunction "F_9") (pintype "input"))
    )
    (net (code "104") (name "/COL6_G") (class "Default")
      (node (ref "CN2") (pin "17") (pinfunction "S_17") (pintype "passive"))
      (node (ref "LED_R1C6") (pin "8") (pinfunction "G_8") (pintype "input"))
      (node (ref "LED_R2C6") (pin "8") (pinfunction "G_8") (pintype "input"))
      (node (ref "LED_R3C6") (pin "8") (pinfunction "G_8") (pintype "input"))
    )
    (net (code "105") (name "/COL6_H") (class "Default")
      (node (ref "CN2") (pin "21") (pinfunction "S_21") (pintype "passive"))
      (node (ref "LED_R1C6") (pin "4") (pinfunction "H_4") (pintype "input"))
      (node (ref "LED_R2C6") (pin "4") (pinfunction "H_4") (pintype "input"))
      (node (ref "LED_R3C6") (pin "4") (pinfunction "H_4") (pintype "input"))
    )
    (net (code "106") (name "/COL6_K") (class "Default")
      (node (ref "CN2") (pin "22") (pinfunction "S_22") (pintype "passive"))
      (node (ref "LED_R1C6") (pin "3") (pinfunction "K_3") (pintype "input"))
      (node (ref "LED_R2C6") (pin "3") (pinfunction "K_3") (pintype "input"))
      (node (ref "LED_R3C6") (pin "3") (pinfunction "K_3") (pintype "input"))
    )
    (net (code "107") (name "/COL6_M") (class "Default")
      (node (ref "CN2") (pin "23") (pinfunction "S_23") (pintype "passive"))
      (node (ref "LED_R1C6") (pin "2") (pinfunction "M_2") (pintype "input"))
      (node (ref "LED_R2C6") (pin "2") (pinfunction "M_2") (pintype "input"))
      (node (ref "LED_R3C6") (pin "2") (pinfunction "M_2") (pintype "input"))
    )
    (net (code "108") (name "/COL6_N") (class "Default")
      (node (ref "CN2") (pin "26") (pinfunction "S_26") (pintype "passive"))
      (node (ref "LED_R1C6") (pin "17") (pinfunction "N_17") (pintype "input"))
      (node (ref "LED_R2C6") (pin "17") (pinfunction "N_17") (pintype "input"))
      (node (ref "LED_R3C6") (pin "17") (pinfunction "N_17") (pintype "input"))
    )
    (net (code "109") (name "/COL6_P") (class "Default")
      (node (ref "CN2") (pin "28") (pinfunction "S_28") (pintype "passive"))
      (node (ref "LED_R1C6") (pin "15") (pinfunction "P_15") (pintype "input"))
      (node (ref "LED_R2C6") (pin "15") (pinfunction "P_15") (pintype "input"))
      (node (ref "LED_R3C6") (pin "15") (pinfunction "P_15") (pintype "input"))
    )
    (net (code "110") (name "/COL6_R") (class "Default")
      (node (ref "CN2") (pin "29") (pinfunction "S_29") (pintype "passive"))
      (node (ref "LED_R1C6") (pin "14") (pinfunction "R_14") (pintype "input"))
      (node (ref "LED_R2C6") (pin "14") (pinfunction "R_14") (pintype "input"))
      (node (ref "LED_R3C6") (pin "14") (pinfunction "R_14") (pintype "input"))
    )
    (net (code "111") (name "/COL6_S") (class "Default")
      (node (ref "CN2") (pin "19") (pinfunction "S_19") (pintype "passive"))
      (node (ref "LED_R1C6") (pin "6") (pinfunction "S_6") (pintype "input"))
      (node (ref "LED_R2C6") (pin "6") (pinfunction "S_6") (pintype "input"))
      (node (ref "LED_R3C6") (pin "6") (pinfunction "S_6") (pintype "input"))
    )
    (net (code "112") (name "/COL6_T") (class "Default")
      (node (ref "CN2") (pin "18") (pinfunction "S_18") (pintype "passive"))
      (node (ref "LED_R1C6") (pin "7") (pinfunction "T_7") (pintype "input"))
      (node (ref "LED_R2C6") (pin "7") (pinfunction "T_7") (pintype "input"))
      (node (ref "LED_R3C6") (pin "7") (pinfunction "T_7") (pintype "input"))
    )
    (net (code "113") (name "/COL6_U") (class "Default")
      (node (ref "CN2") (pin "20") (pinfunction "S_20") (pintype "passive"))
      (node (ref "LED_R1C6") (pin "5") (pinfunction "U_5") (pintype "input"))
      (node (ref "LED_R2C6") (pin "5") (pinfunction "U_5") (pintype "input"))
      (node (ref "LED_R3C6") (pin "5") (pinfunction "U_5") (pintype "input"))
    )
    (net (code "114") (name "/COL7_A") (class "Default")
      (node (ref "CN2") (pin "40") (pinfunction "S_40") (pintype "passive"))
      (node (ref "LED_R1C7") (pin "1") (pinfunction "A_1") (pintype "input"))
      (node (ref "LED_R2C7") (pin "1") (pinfunction "A_1") (pintype "input"))
      (node (ref "LED_R3C7") (pin "1") (pinfunction "A_1") (pintype "input"))
    )
    (net (code "115") (name "/COL7_B") (class "Default")
      (node (ref "CN4") (pin "20") (pinfunction "S_20") (pintype "passive"))
      (node (ref "LED_R1C7") (pin "18") (pinfunction "B_18") (pintype "input"))
      (node (ref "LED_R2C7") (pin "18") (pinfunction "B_18") (pintype "input"))
      (node (ref "LED_R3C7") (pin "18") (pinfunction "B_18") (pintype "input"))
    )
    (net (code "116") (name "/COL7_C") (class "Default")
      (node (ref "CN4") (pin "18") (pinfunction "S_18") (pintype "passive"))
      (node (ref "LED_R1C7") (pin "16") (pinfunction "C_16") (pintype "input"))
      (node (ref "LED_R2C7") (pin "16") (pinfunction "C_16") (pintype "input"))
      (node (ref "LED_R3C7") (pin "16") (pinfunction "C_16") (pintype "input"))
    )
    (net (code "117") (name "/COL7_D") (class "Default")
      (node (ref "CN4") (pin "23") (pinfunction "S_23") (pintype "passive"))
      (node (ref "LED_R1C7") (pin "13") (pinfunction "D_13") (pintype "input"))
      (node (ref "LED_R2C7") (pin "13") (pinfunction "D_13") (pintype "input"))
      (node (ref "LED_R3C7") (pin "13") (pinfunction "D_13") (pintype "input"))
    )
    (net (code "118") (name "/COL7_E") (class "Default")
      (node (ref "CN4") (pin "22") (pinfunction "S_22") (pintype "passive"))
      (node (ref "LED_R1C7") (pin "10") (pinfunction "E_10") (pintype "input"))
      (node (ref "LED_R2C7") (pin "10") (pinfunction "E_10") (pintype "input"))
      (node (ref "LED_R3C7") (pin "10") (pinfunction "E_10") (pintype "input"))
    )
    (net (code "119") (name "/COL7_F") (class "Default")
      (node (ref "CN4") (pin "21") (pinfunction "S_21") (pintype "passive"))
      (node (ref "LED_R1C7") (pin "9") (pinfunction "F_9") (pintype "input"))
      (node (ref "LED_R2C7") (pin "9") (pinfunction "F_9") (pintype "input"))
      (node (ref "LED_R3C7") (pin "9") (pinfunction "F_9") (pintype "input"))
    )
    (net (code "120") (name "/COL7_G") (class "Default")
      (node (ref "CN2") (pin "33") (pinfunction "S_33") (pintype "passive"))
      (node (ref "LED_R1C7") (pin "8") (pinfunction "G_8") (pintype "input"))
      (node (ref "LED_R2C7") (pin "8") (pinfunction "G_8") (pintype "input"))
      (node (ref "LED_R3C7") (pin "8") (pinfunction "G_8") (pintype "input"))
    )
    (net (code "121") (name "/COL7_H") (class "Default")
      (node (ref "CN2") (pin "37") (pinfunction "S_37") (pintype "passive"))
      (node (ref "LED_R1C7") (pin "4") (pinfunction "H_4") (pintype "input"))
      (node (ref "LED_R2C7") (pin "4") (pinfunction "H_4") (pintype "input"))
      (node (ref "LED_R3C7") (pin "4") (pinfunction "H_4") (pintype "input"))
    )
    (net (code "122") (name "/COL7_K") (class "Default")
      (node (ref "CN2") (pin "38") (pinfunction "S_38") (pintype "passive"))
      (node (ref "LED_R1C7") (pin "3") (pinfunction "K_3") (pintype "input"))
      (node (ref "LED_R2C7") (pin "3") (pinfunction "K_3") (pintype "input"))
      (node (ref "LED_R3C7") (pin "3") (pinfunction "K_3") (pintype "input"))
    )
    (net (code "123") (name "/COL7_M") (class "Default")
      (node (ref "CN2") (pin "39") (pinfunction "S_39") (pintype "passive"))
      (node (ref "LED_R1C7") (pin "2") (pinfunction "M_2") (pintype "input"))
      (node (ref "LED_R2C7") (pin "2") (pinfunction "M_2") (pintype "input"))
      (node (ref "LED_R3C7") (pin "2") (pinfunction "M_2") (pintype "input"))
    )
    (net (code "124") (name "/COL7_N") (class "Default")
      (node (ref "CN4") (pin "19") (pinfunction "S_19") (pintype "passive"))
      (node (ref "LED_R1C7") (pin "17") (pinfunction "N_17") (pintype "input"))
      (node (ref "LED_R2C7") (pin "17") (pinfunction "N_17") (pintype "input"))
      (node (ref "LED_R3C7") (pin "17") (pinfunction "N_17") (pintype "input"))
    )
    (net (code "125") (name "/COL7_P") (class "Default")
      (node (ref "CN4") (pin "17") (pinfunction "S_17") (pintype "passive"))
      (node (ref "LED_R1C7") (pin "15") (pinfunction "P_15") (pintype "input"))
      (node (ref "LED_R2C7") (pin "15") (pinfunction "P_15") (pintype "input"))
      (node (ref "LED_R3C7") (pin "15") (pinfunction "P_15") (pintype "input"))
    )
    (net (code "126") (name "/COL7_R") (class "Default")
      (node (ref "CN4") (pin "24") (pinfunction "S_24") (pintype "passive"))
      (node (ref "LED_R1C7") (pin "14") (pinfunction "R_14") (pintype "input"))
      (node (ref "LED_R2C7") (pin "14") (pinfunction "R_14") (pintype "input"))
      (node (ref "LED_R3C7") (pin "14") (pinfunction "R_14") (pintype "input"))
    )
    (net (code "127") (name "/COL7_S") (class "Default")
      (node (ref "CN2") (pin "35") (pinfunction "S_35") (pintype "passive"))
      (node (ref "LED_R1C7") (pin "6") (pinfunction "S_6") (pintype "input"))
      (node (ref "LED_R2C7") (pin "6") (pinfunction "S_6") (pintype "input"))
      (node (ref "LED_R3C7") (pin "6") (pinfunction "S_6") (pintype "input"))
    )
    (net (code "128") (name "/COL7_T") (class "Default")
      (node (ref "CN2") (pin "34") (pinfunction "S_34") (pintype "passive"))
      (node (ref "LED_R1C7") (pin "7") (pinfunction "T_7") (pintype "input"))
      (node (ref "LED_R2C7") (pin "7") (pinfunction "T_7") (pintype "input"))
      (node (ref "LED_R3C7") (pin "7") (pinfunction "T_7") (pintype "input"))
    )
    (net (code "129") (name "/COL7_U") (class "Default")
      (node (ref "CN2") (pin "36") (pinfunction "S_36") (pintype "passive"))
      (node (ref "LED_R1C7") (pin "5") (pinfunction "U_5") (pintype "input"))
      (node (ref "LED_R2C7") (pin "5") (pinfunction "U_5") (pintype "input"))
      (node (ref "LED_R3C7") (pin "5") (pinfunction "U_5") (pintype "input"))
    )
    (net (code "130") (name "/DP0") (class "Default")
      (node (ref "CN1") (pin "8") (pinfunction "S_8") (pintype "passive"))
      (node (ref "LED_R1C0") (pin "12") (pinfunction "DP_12") (pintype "input"))
      (node (ref "LED_R2C0") (pin "12") (pinfunction "DP_12") (pintype "input"))
      (node (ref "LED_R3C0") (pin "12") (pinfunction "DP_12") (pintype "input"))
    )
    (net (code "131") (name "/DP1") (class "Default")
      (node (ref "CN1") (pin "7") (pinfunction "S_7") (pintype "passive"))
      (node (ref "LED_R1C1") (pin "12") (pinfunction "DP_12") (pintype "input"))
      (node (ref "LED_R2C1") (pin "12") (pinfunction "DP_12") (pintype "input"))
      (node (ref "LED_R3C1") (pin "12") (pinfunction "DP_12") (pintype "input"))
    )
    (net (code "132") (name "/DP2") (class "Default")
      (node (ref "CN1") (pin "6") (pinfunction "S_6") (pintype "passive"))
      (node (ref "LED_R1C2") (pin "12") (pinfunction "DP_12") (pintype "input"))
      (node (ref "LED_R2C2") (pin "12") (pinfunction "DP_12") (pintype "input"))
      (node (ref "LED_R3C2") (pin "12") (pinfunction "DP_12") (pintype "input"))
    )
    (net (code "133") (name "/DP3") (class "Default")
      (node (ref "CN1") (pin "5") (pinfunction "S_5") (pintype "passive"))
      (node (ref "LED_R1C3") (pin "12") (pinfunction "DP_12") (pintype "input"))
      (node (ref "LED_R2C3") (pin "12") (pinfunction "DP_12") (pintype "input"))
      (node (ref "LED_R3C3") (pin "12") (pinfunction "DP_12") (pintype "input"))
    )
    (net (code "134") (name "/DP4") (class "Default")
      (node (ref "CN1") (pin "4") (pinfunction "S_4") (pintype "passive"))
      (node (ref "LED_R1C4") (pin "12") (pinfunction "DP_12") (pintype "input"))
      (node (ref "LED_R2C4") (pin "12") (pinfunction "DP_12") (pintype "input"))
      (node (ref "LED_R3C4") (pin "12") (pinfunction "DP_12") (pintype "input"))
    )
    (net (code "135") (name "/DP5") (class "Default")
      (node (ref "CN1") (pin "3") (pinfunction "S_3") (pintype "passive"))
      (node (ref "LED_R1C5") (pin "12") (pinfunction "DP_12") (pintype "input"))
      (node (ref "LED_R2C5") (pin "12") (pinfunction "DP_12") (pintype "input"))
      (node (ref "LED_R3C5") (pin "12") (pinfunction "DP_12") (pintype "input"))
    )
    (net (code "136") (name "/DP6") (class "Default")
      (node (ref "CN1") (pin "2") (pinfunction "S_2") (pintype "passive"))
      (node (ref "LED_R1C6") (pin "12") (pinfunction "DP_12") (pintype "input"))
      (node (ref "LED_R2C6") (pin "12") (pinfunction "DP_12") (pintype "input"))
      (node (ref "LED_R3C6") (pin "12") (pinfunction "DP_12") (pintype "input"))
    )
    (net (code "137") (name "/DP7") (class "Default")
      (node (ref "CN1") (pin "1") (pinfunction "S_1") (pintype "passive"))
      (node (ref "LED_R1C7") (pin "12") (pinfunction "DP_12") (pintype "input"))
      (node (ref "LED_R2C7") (pin "12") (pinfunction "DP_12") (pintype "input"))
      (node (ref "LED_R3C7") (pin "12") (pinfunction "DP_12") (pintype "input"))
    )
    (net (code "138") (name "GND") (class "Default")
      (node (ref "CN4") (pin "37") (pinfunction "S_37") (pintype "passive"))
      (node (ref "CN4") (pin "39") (pinfunction "S_39") (pintype "passive"))
    )
    (net (code "139") (name "Net-(CN4AB-S)") (class "Default")
      (node (ref "CN4") (pin "34") (pinfunction "S_34") (pintype "passive"))
      (node (ref "R1") (pin "1") (pinfunction "1_1") (pintype "passive"))
    )
    (net (code "140") (name "Net-(CN4AC-S)") (class "Default")
      (node (ref "CN4") (pin "35") (pinfunction "S_35") (pintype "passive"))
      (node (ref "R2") (pin "1") (pinfunction "1_1") (pintype "passive"))
    )
    (net (code "141") (name "Net-(CN4AD-S)") (class "Default")
      (node (ref "CN4") (pin "36") (pinfunction "S_36") (pintype "passive"))
      (node (ref "R3") (pin "1") (pinfunction "1_1") (pintype "passive"))
    )
    (net (code "142") (name "Net-(Q1-PadB)") (class "Default")
      (node (ref "Q1") (pin "B") (pinfunction "B_B") (pintype "passive"))
      (node (ref "R1") (pin "2") (pinfunction "2_2") (pintype "passive"))
    )
    (net (code "143") (name "Net-(Q2-PadB)") (class "Default")
      (node (ref "Q2") (pin "B") (pinfunction "B_B") (pintype "passive"))
      (node (ref "R2") (pin "2") (pinfunction "2_2") (pintype "passive"))
    )
    (net (code "144") (name "Net-(Q3-PadB)") (class "Default")
      (node (ref "Q3") (pin "B") (pinfunction "B_B") (pintype "passive"))
      (node (ref "R3") (pin "2") (pinfunction "2_2") (pintype "passive"))
    )
    (net (code "145") (name "R1_PWR") (class "Default")
      (node (ref "LED_R1C0") (pin "11") (pinfunction "CA_11") (pintype "power_in"))
      (node (ref "LED_R1C1") (pin "11") (pinfunction "CA_11") (pintype "power_in"))
      (node (ref "LED_R1C2") (pin "11") (pinfunction "CA_11") (pintype "power_in"))
      (node (ref "LED_R1C3") (pin "11") (pinfunction "CA_11") (pintype "power_in"))
      (node (ref "LED_R1C4") (pin "11") (pinfunction "CA_11") (pintype "power_in"))
      (node (ref "LED_R1C5") (pin "11") (pinfunction "CA_11") (pintype "power_in"))
      (node (ref "LED_R1C6") (pin "11") (pinfunction "CA_11") (pintype "power_in"))
      (node (ref "LED_R1C7") (pin "11") (pinfunction "CA_11") (pintype "power_in"))
      (node (ref "Q1") (pin "C") (pinfunction "C_C") (pintype "passive"))
    )
    (net (code "146") (name "R2_PWR") (class "Default")
      (node (ref "LED_R2C0") (pin "11") (pinfunction "CA_11") (pintype "power_in"))
      (node (ref "LED_R2C1") (pin "11") (pinfunction "CA_11") (pintype "power_in"))
      (node (ref "LED_R2C2") (pin "11") (pinfunction "CA_11") (pintype "power_in"))
      (node (ref "LED_R2C3") (pin "11") (pinfunction "CA_11") (pintype "power_in"))
      (node (ref "LED_R2C4") (pin "11") (pinfunction "CA_11") (pintype "power_in"))
      (node (ref "LED_R2C5") (pin "11") (pinfunction "CA_11") (pintype "power_in"))
      (node (ref "LED_R2C6") (pin "11") (pinfunction "CA_11") (pintype "power_in"))
      (node (ref "LED_R2C7") (pin "11") (pinfunction "CA_11") (pintype "power_in"))
      (node (ref "Q2") (pin "C") (pinfunction "C_C") (pintype "passive"))
    )
    (net (code "147") (name "R3_PWR") (class "Default")
      (node (ref "LED_R3C0") (pin "11") (pinfunction "CA_11") (pintype "power_in"))
      (node (ref "LED_R3C1") (pin "11") (pinfunction "CA_11") (pintype "power_in"))
      (node (ref "LED_R3C2") (pin "11") (pinfunction "CA_11") (pintype "power_in"))
      (node (ref "LED_R3C3") (pin "11") (pinfunction "CA_11") (pintype "power_in"))
      (node (ref "LED_R3C4") (pin "11") (pinfunction "CA_11") (pintype "power_in"))
      (node (ref "LED_R3C5") (pin "11") (pinfunction "CA_11") (pintype "power_in"))
      (node (ref "LED_R3C6") (pin "11") (pinfunction "CA_11") (pintype "power_in"))
      (node (ref "LED_R3C7") (pin "11") (pinfunction "CA_11") (pintype "power_in"))
      (node (ref "Q3") (pin "C") (pinfunction "C_C") (pintype "passive"))
    )
    (net (code "148") (name "unconnected-(CN3I-S-Pad17)") (class "Default")
      (node (ref "CN3") (pin "17") (pinfunction "S_17") (pintype "passive"))
    )
    (net (code "149") (name "unconnected-(CN3J-S-Pad18)") (class "Default")
      (node (ref "CN3") (pin "18") (pinfunction "S_18") (pintype "passive"))
    )
    (net (code "150") (name "unconnected-(CN3K-S-Pad19)") (class "Default")
      (node (ref "CN3") (pin "19") (pinfunction "S_19") (pintype "passive"))
    )
    (net (code "151") (name "unconnected-(CN3M-S-Pad20)") (class "Default")
      (node (ref "CN3") (pin "20") (pinfunction "S_20") (pintype "passive"))
    )
    (net (code "152") (name "unconnected-(CN3N-S-Pad21)") (class "Default")
      (node (ref "CN3") (pin "21") (pinfunction "S_21") (pintype "passive"))
    )
    (net (code "153") (name "unconnected-(CN3O-S-Pad22)") (class "Default")
      (node (ref "CN3") (pin "22") (pinfunction "S_22") (pintype "passive"))
    )
    (net (code "154") (name "unconnected-(CN3P-S-Pad23)") (class "Default")
      (node (ref "CN3") (pin "23") (pinfunction "S_23") (pintype "passive"))
    )
    (net (code "155") (name "unconnected-(CN3Q-S-Pad24)") (class "Default")
      (node (ref "CN3") (pin "24") (pinfunction "S_24") (pintype "passive"))
    )
    (net (code "156") (name "unconnected-(CN4AA-S-Pad33)") (class "Default")
      (node (ref "CN4") (pin "33") (pinfunction "S_33") (pintype "passive"))
    )
    (net (code "157") (name "unconnected-(CN4R-S-Pad25)") (class "Default")
      (node (ref "CN4") (pin "25") (pinfunction "S_25") (pintype "passive"))
    )
    (net (code "158") (name "unconnected-(CN4S-S-Pad26)") (class "Default")
      (node (ref "CN4") (pin "26") (pinfunction "S_26") (pintype "passive"))
    )
    (net (code "159") (name "unconnected-(CN4T-S-Pad27)") (class "Default")
      (node (ref "CN4") (pin "27") (pinfunction "S_27") (pintype "passive"))
    )
    (net (code "160") (name "unconnected-(CN4U-S-Pad28)") (class "Default")
      (node (ref "CN4") (pin "28") (pinfunction "S_28") (pintype "passive"))
    )
    (net (code "161") (name "unconnected-(CN4V-S-Pad29)") (class "Default")
      (node (ref "CN4") (pin "29") (pinfunction "S_29") (pintype "passive"))
    )
    (net (code "162") (name "unconnected-(CN4X-S-Pad30)") (class "Default")
      (node (ref "CN4") (pin "30") (pinfunction "S_30") (pintype "passive"))
    )
    (net (code "163") (name "unconnected-(CN4Y-S-Pad31)") (class "Default")
      (node (ref "CN4") (pin "31") (pinfunction "S_31") (pintype "passive"))
    )
    (net (code "164") (name "unconnected-(CN4Z-S-Pad32)") (class "Default")
      (node (ref "CN4") (pin "32") (pinfunction "S_32") (pintype "passive"))
    )
  )
)
